# es11quematico_tesis_brd.net
KiCad netlist of a schematic drawn in EAGLE
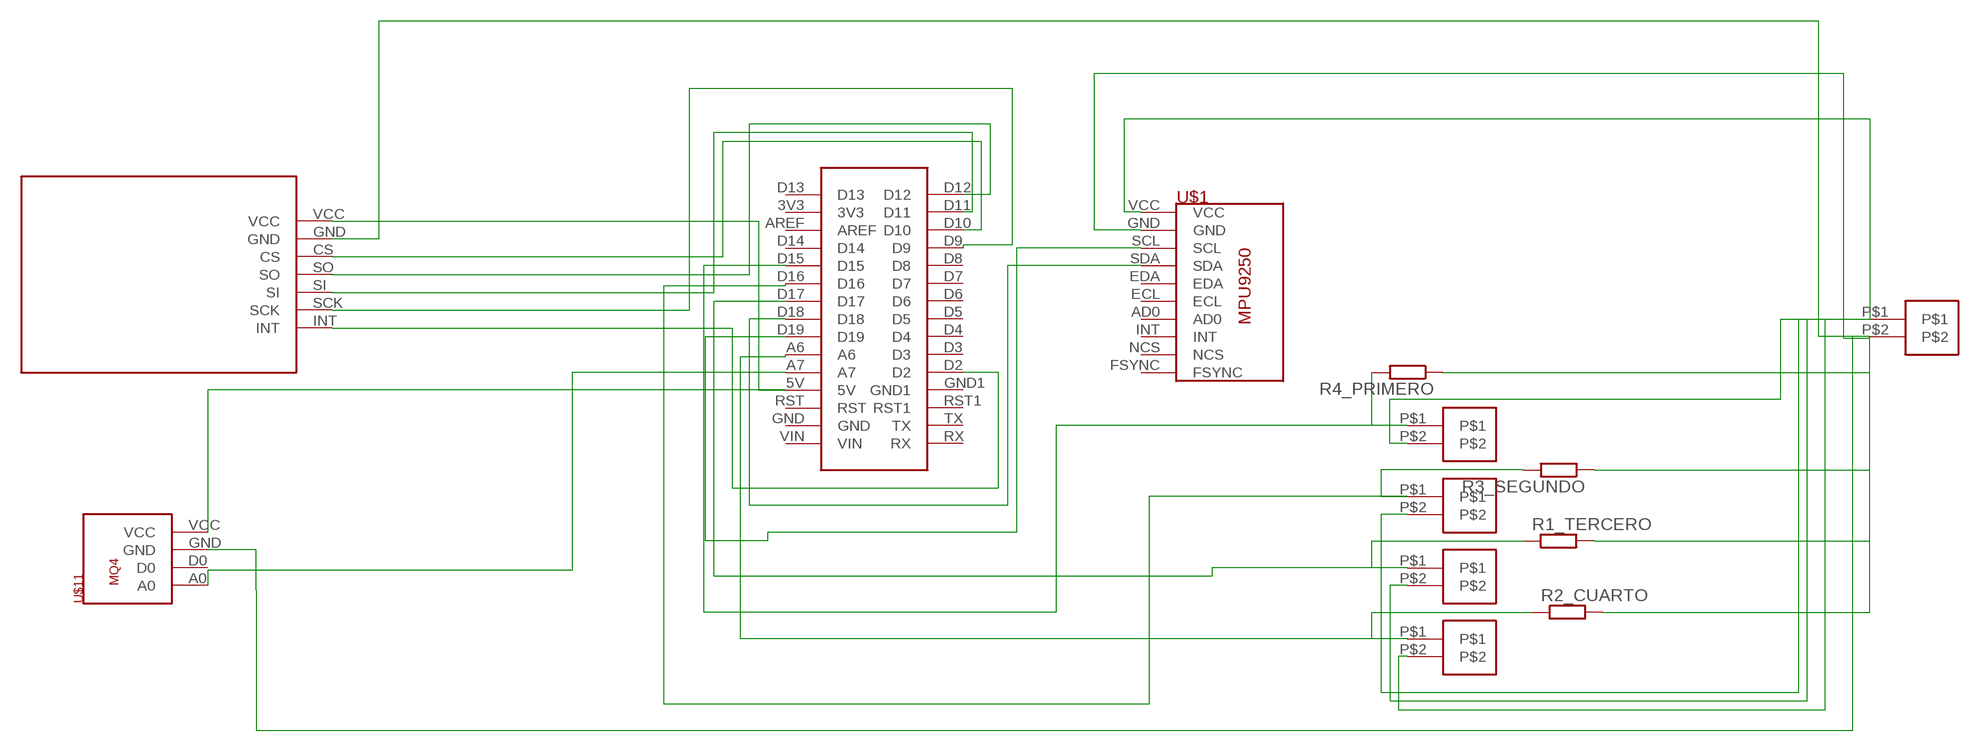
[diagram p0: schematic, sheet 1]

(export (version "E")
  (design (tool "Eeschema 10.0.6"))
  (components
    (comp (ref "ALIMENTACION")
      (value "FSR402")
      (footprint "eagle-import:FSR402")
      (libsource (lib "eagle-import") (part "FSR402"))
    )
    (comp (ref "CUARTO_FSR")
      (value "FSR402")
      (footprint "eagle-import:FSR402")
      (libsource (lib "eagle-import") (part "FSR402"))
    )
    (comp (ref "PRIMER_FSR")
      (value "FSR402")
      (footprint "eagle-import:FSR402")
      (libsource (lib "eagle-import") (part "FSR402"))
    )
    (comp (ref "R1_TERCERO")
      (value "R-EU_0613/5V")
      (footprint "eagle-import:P0613V")
      (libsource (lib "eagle-import") (part "R-EU_0613/5V"))
    )
    (comp (ref "R2_CUARTO")
      (value "R-EU_0613/5V")
      (footprint "eagle-import:P0613V")
      (libsource (lib "eagle-import") (part "R-EU_0613/5V"))
    )
    (comp (ref "R3_SEGUNDO")
      (value "R-EU_0613/5V")
      (footprint "eagle-import:P0613V")
      (libsource (lib "eagle-import") (part "R-EU_0613/5V"))
    )
    (comp (ref "R4_PRIMERO")
      (value "R-EU_0613/5V")
      (footprint "eagle-import:P0613V")
      (libsource (lib "eagle-import") (part "R-EU_0613/5V"))
    )
    (comp (ref "SEGUNDO_FSR")
      (value "FSR402")
      (footprint "eagle-import:FSR402")
      (libsource (lib "eagle-import") (part "FSR402"))
    )
    (comp (ref "TERCER_FSR")
      (value "FSR402")
      (footprint "eagle-import:FSR402")
      (libsource (lib "eagle-import") (part "FSR402"))
    )
    (comp (ref "U$1")
      (value "MPU9250")
      (footprint "eagle-import:MPU9250")
      (libsource (lib "eagle-import") (part "MPU9250"))
    )
    (comp (ref "U$2")
      (value "ARDUINO-NANO")
      (footprint "eagle-import:ARDUINO-NANO")
      (libsource (lib "eagle-import") (part "ARDUINO-NANO"))
    )
    (comp (ref "U$8")
      (value "MCP2515")
      (footprint "eagle-import:MCP2515")
      (libsource (lib "eagle-import") (part "MCP2515"))
    )
    (comp (ref "U$11")
      (value "MQ4")
      (footprint "eagle-import:MQ4")
      (libsource (lib "eagle-import") (part "MQ4"))
    )
  )
  (nets
    (net (code "1") (name "Net-(ALIMENTACION-PadP$1)") (class "Default")
      (node (ref "ALIMENTACION") (pin "P$1") (pinfunction "P$1_P$1") (pintype "bidirectional"))
      (node (ref "CUARTO_FSR") (pin "P$2") (pinfunction "P$2_P$2") (pintype "bidirectional"))
      (node (ref "PRIMER_FSR") (pin "P$2") (pinfunction "P$2_P$2") (pintype "bidirectional"))
      (node (ref "SEGUNDO_FSR") (pin "P$2") (pinfunction "P$2_P$2") (pintype "bidirectional"))
      (node (ref "TERCER_FSR") (pin "P$2") (pinfunction "P$2_P$2") (pintype "bidirectional"))
      (node (ref "U$1") (pin "VCC") (pinfunction "VCC_VCC") (pintype "bidirectional"))
    )
    (net (code "2") (name "Net-(ALIMENTACION-PadP$2)") (class "Default")
      (node (ref "ALIMENTACION") (pin "P$2") (pinfunction "P$2_P$2") (pintype "bidirectional"))
      (node (ref "R1_TERCERO") (pin "2") (pinfunction "2_2") (pintype "passive"))
      (node (ref "R2_CUARTO") (pin "2") (pinfunction "2_2") (pintype "passive"))
      (node (ref "R3_SEGUNDO") (pin "1") (pinfunction "1_1") (pintype "passive"))
      (node (ref "R4_PRIMERO") (pin "1") (pinfunction "1_1") (pintype "passive"))
      (node (ref "U$1") (pin "GND") (pinfunction "GND_GND") (pintype "bidirectional"))
      (node (ref "U$11") (pin "GND") (pinfunction "GND_GND") (pintype "bidirectional"))
      (node (ref "U$8") (pin "GND") (pinfunction "GND_GND") (pintype "bidirectional"))
    )
    (net (code "3") (name "Net-(CUARTO_FSR-PadP$1)") (class "Default")
      (node (ref "CUARTO_FSR") (pin "P$1") (pinfunction "P$1_P$1") (pintype "bidirectional"))
      (node (ref "R2_CUARTO") (pin "1") (pinfunction "1_1") (pintype "passive"))
      (node (ref "U$2") (pin "A6") (pinfunction "A6_A6") (pintype "bidirectional"))
    )
    (net (code "4") (name "Net-(PRIMER_FSR-PadP$1)") (class "Default")
      (node (ref "PRIMER_FSR") (pin "P$1") (pinfunction "P$1_P$1") (pintype "bidirectional"))
      (node (ref "R4_PRIMERO") (pin "2") (pinfunction "2_2") (pintype "passive"))
      (node (ref "U$2") (pin "D15") (pinfunction "D15_D15") (pintype "bidirectional"))
    )
    (net (code "5") (name "Net-(R1_TERCERO-Pad1)") (class "Default")
      (node (ref "R1_TERCERO") (pin "1") (pinfunction "1_1") (pintype "passive"))
      (node (ref "TERCER_FSR") (pin "P$1") (pinfunction "P$1_P$1") (pintype "bidirectional"))
      (node (ref "U$2") (pin "D17") (pinfunction "D17_D17") (pintype "bidirectional"))
    )
    (net (code "6") (name "Net-(R3_SEGUNDO-Pad2)") (class "Default")
      (node (ref "R3_SEGUNDO") (pin "2") (pinfunction "2_2") (pintype "passive"))
      (node (ref "SEGUNDO_FSR") (pin "P$1") (pinfunction "P$1_P$1") (pintype "bidirectional"))
      (node (ref "U$2") (pin "D16") (pinfunction "D16_D16") (pintype "bidirectional"))
    )
    (net (code "7") (name "Net-(U$1-PadSCL)") (class "Default")
      (node (ref "U$1") (pin "SCL") (pinfunction "SCL_SCL") (pintype "bidirectional"))
      (node (ref "U$2") (pin "D19") (pinfunction "D19_D19") (pintype "bidirectional"))
    )
    (net (code "8") (name "Net-(U$1-PadSDA)") (class "Default")
      (node (ref "U$1") (pin "SDA") (pinfunction "SDA_SDA") (pintype "bidirectional"))
      (node (ref "U$2") (pin "D18") (pinfunction "D18_D18") (pintype "bidirectional"))
    )
    (net (code "9") (name "Net-(U$2-PadD2)") (class "Default")
      (node (ref "U$2") (pin "D2") (pinfunction "D2_D2") (pintype "bidirectional"))
      (node (ref "U$8") (pin "INT") (pinfunction "INT_INT") (pintype "bidirectional"))
    )
    (net (code "10") (name "Net-(U$2-PadD9)") (class "Default")
      (node (ref "U$2") (pin "D9") (pinfunction "D9_D9") (pintype "bidirectional"))
      (node (ref "U$8") (pin "SCK") (pinfunction "SCK_SCK") (pintype "bidirectional"))
    )
    (net (code "11") (name "Net-(U$2-PadD10)") (class "Default")
      (node (ref "U$2") (pin "D10") (pinfunction "D10_D10") (pintype "bidirectional"))
      (node (ref "U$8") (pin "CS") (pinfunction "CS_CS") (pintype "bidirectional"))
    )
    (net (code "12") (name "Net-(U$2-PadD11)") (class "Default")
      (node (ref "U$2") (pin "D11") (pinfunction "D11_D11") (pintype "bidirectional"))
      (node (ref "U$8") (pin "SI") (pinfunction "SI_SI") (pintype "bidirectional"))
    )
    (net (code "13") (name "Net-(U$2-PadD12)") (class "Default")
      (node (ref "U$2") (pin "D12") (pinfunction "D12_D12") (pintype "bidirectional"))
      (node (ref "U$8") (pin "SO") (pinfunction "SO_SO") (pintype "bidirectional"))
    )
    (net (code "14") (name "Net-(U$11-PadA0)") (class "Default")
      (node (ref "U$11") (pin "A0") (pinfunction "A0_A0") (pintype "bidirectional"))
      (node (ref "U$2") (pin "A7") (pinfunction "A7_A7") (pintype "bidirectional"))
    )
    (net (code "15") (name "Net-(U$11-PadVCC)") (class "Default")
      (node (ref "U$11") (pin "VCC") (pinfunction "VCC_VCC") (pintype "bidirectional"))
      (node (ref "U$2") (pin "5V") (pinfunction "5V_5V") (pintype "bidirectional"))
      (node (ref "U$8") (pin "VCC") (pinfunction "VCC_VCC") (pintype "bidirectional"))
    )
    (net (code "16") (name "unconnected-(U$1-PadAD0)") (class "Default")
      (node (ref "U$1") (pin "AD0") (pinfunction "AD0_AD0") (pintype "bidirectional"))
    )
    (net (code "17") (name "unconnected-(U$1-PadECL)") (class "Default")
      (node (ref "U$1") (pin "ECL") (pinfunction "ECL_ECL") (pintype "bidirectional"))
    )
    (net (code "18") (name "unconnected-(U$1-PadEDA)") (class "Default")
      (node (ref "U$1") (pin "EDA") (pinfunction "EDA_EDA") (pintype "bidirectional"))
    )
    (net (code "19") (name "unconnected-(U$1-PadFSYNC)") (class "Default")
      (node (ref "U$1") (pin "FSYNC") (pinfunction "FSYNC_FSYNC") (pintype "bidirectional"))
    )
    (net (code "20") (name "unconnected-(U$1-PadINT)") (class "Default")
      (node (ref "U$1") (pin "INT") (pinfunction "INT_INT") (pintype "bidirectional"))
    )
    (net (code "21") (name "unconnected-(U$1-PadNCS)") (class "Default")
      (node (ref "U$1") (pin "NCS") (pinfunction "NCS_NCS") (pintype "bidirectional"))
    )
    (net (code "22") (name "unconnected-(U$2-Pad3V3)") (class "Default")
      (node (ref "U$2") (pin "3V3") (pinfunction "3V3_3V3") (pintype "bidirectional"))
    )
    (net (code "23") (name "unconnected-(U$2-PadAREF)") (class "Default")
      (node (ref "U$2") (pin "AREF") (pinfunction "AREF_AREF") (pintype "bidirectional"))
    )
    (net (code "24") (name "unconnected-(U$2-PadD3)") (class "Default")
      (node (ref "U$2") (pin "D3") (pinfunction "D3_D3") (pintype "bidirectional"))
    )
    (net (code "25") (name "unconnected-(U$2-PadD4)") (class "Default")
      (node (ref "U$2") (pin "D4") (pinfunction "D4_D4") (pintype "bidirectional"))
    )
    (net (code "26") (name "unconnected-(U$2-PadD5)") (class "Default")
      (node (ref "U$2") (pin "D5") (pinfunction "D5_D5") (pintype "bidirectional"))
    )
    (net (code "27") (name "unconnected-(U$2-PadD6)") (class "Default")
      (node (ref "U$2") (pin "D6") (pinfunction "D6_D6") (pintype "bidirectional"))
    )
    (net (code "28") (name "unconnected-(U$2-PadD7)") (class "Default")
      (node (ref "U$2") (pin "D7") (pinfunction "D7_D7") (pintype "bidirectional"))
    )
    (net (code "29") (name "unconnected-(U$2-PadD8)") (class "Default")
      (node (ref "U$2") (pin "D8") (pinfunction "D8_D8") (pintype "bidirectional"))
    )
    (net (code "30") (name "unconnected-(U$2-PadD13)") (class "Default")
      (node (ref "U$2") (pin "D13") (pinfunction "D13_D13") (pintype "bidirectional"))
    )
    (net (code "31") (name "unconnected-(U$2-PadD14)") (class "Default")
      (node (ref "U$2") (pin "D14") (pinfunction "D14_D14") (pintype "bidirectional"))
    )
    (net (code "32") (name "unconnected-(U$2-PadGND)") (class "Default")
      (node (ref "U$2") (pin "GND") (pinfunction "GND_GND") (pintype "bidirectional"))
    )
    (net (code "33") (name "unconnected-(U$2-PadGND1)") (class "Default")
      (node (ref "U$2") (pin "GND1") (pinfunction "GND1_GND1") (pintype "bidirectional"))
    )
    (net (code "34") (name "unconnected-(U$2-PadRST)") (class "Default")
      (node (ref "U$2") (pin "RST") (pinfunction "RST_RST") (pintype "bidirectional"))
    )
    (net (code "35") (name "unconnected-(U$2-PadRST1)") (class "Default")
      (node (ref "U$2") (pin "RST1") (pinfunction "RST1_RST1") (pintype "bidirectional"))
    )
    (net (code "36") (name "unconnected-(U$2-PadRX)") (class "Default")
      (node (ref "U$2") (pin "RX") (pinfunction "RX_RX") (pintype "bidirectional"))
    )
    (net (code "37") (name "unconnected-(U$2-PadTX)") (class "Default")
      (node (ref "U$2") (pin "TX") (pinfunction "TX_TX") (pintype "bidirectional"))
    )
    (net (code "38") (name "unconnected-(U$2-PadVIN)") (class "Default")
      (node (ref "U$2") (pin "VIN") (pinfunction "VIN_VIN") (pintype "bidirectional"))
    )
    (net (code "39") (name "unconnected-(U$11-PadD0)") (class "Default")
      (node (ref "U$11") (pin "D0") (pinfunction "D0_D0") (pintype "bidirectional"))
    )
  )
)
